# SH8_-_FORCE_SENSITIVE_RESISTOR.net
KiCad netlist of a schematic drawn in Altium Designer
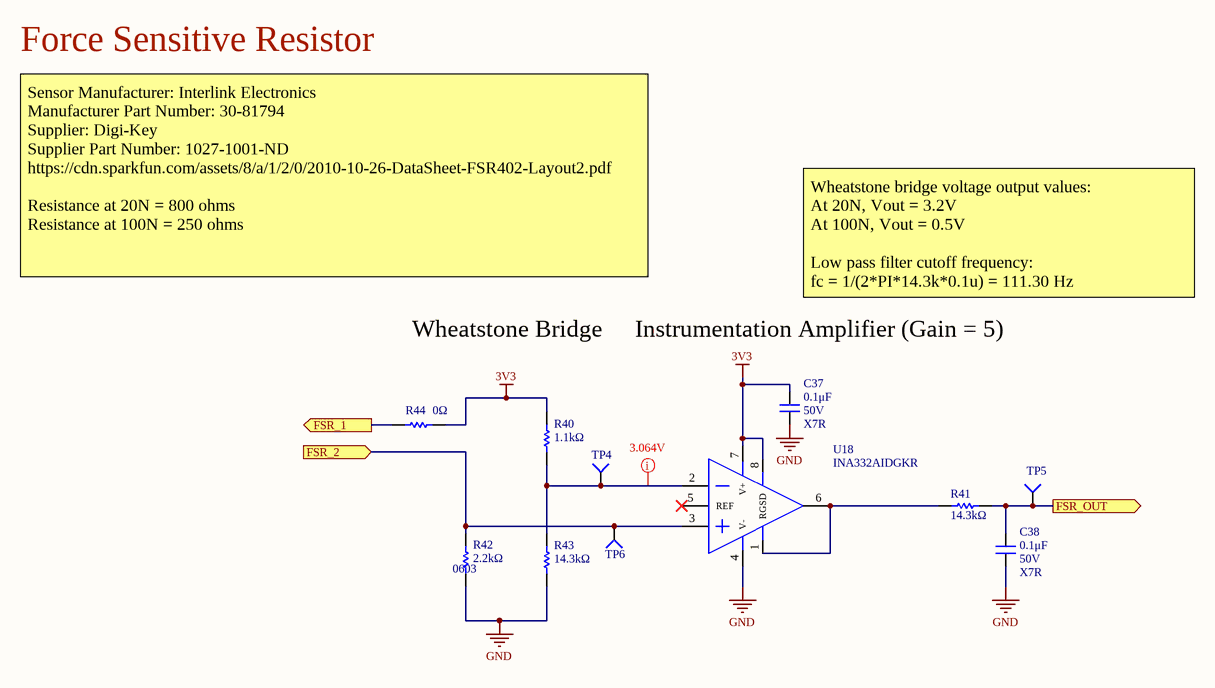
[diagram p0: SH8 - FORCE SENSITIVE RESISTOR.SchDoc]

(export (version "E")
  (design (tool "Eeschema 10.0.6"))
  (components
    (comp (ref "C37")
      (value "0.1μF")
      (footprint "CAP0603")
      (description "CAP CER 0.1UF 50V X7R 0603")
      (fields
        (field (name "VOLTAGE RATING") "50V")
        (field (name "DIELECTRIC") "X7R")
        (field (name "Comment") "CAP_0.1uF_50V_0603")
      )
      (libsource (lib "UWRT_Schematic_Library_2020") (part "CAP_0.1uF_50V_0603"))
    )
    (comp (ref "C38")
      (value "0.1μF")
      (footprint "CAP0603")
      (description "CAP CER 0.1UF 50V X7R 0603")
      (fields
        (field (name "VOLTAGE RATING") "50V")
        (field (name "DIELECTRIC") "X7R")
        (field (name "Comment") "CAP_0.1uF_50V_0603")
      )
      (libsource (lib "UWRT_Schematic_Library_2020") (part "CAP_0.1uF_50V_0603"))
    )
    (comp (ref "R40")
      (value "1.1kΩ")
      (footprint "RESC0603")
      (description "RES 1.1K OHM 1% 1/10W 0603")
      (fields (field (name "Comment") "RES_1.1kΩ_0603_1%"))
      (libsource (lib "UWRT_Schematic_Library_2020") (part "RES_1.1kΩ_0603_1%"))
    )
    (comp (ref "R41")
      (value "14.3kΩ")
      (footprint "RESC0603")
      (description "RES 14.3K OHM 1% 1/10W 0603")
      (fields (field (name "Comment") "RES_14.3kΩ_0603_1%"))
      (libsource (lib "UWRT_Schematic_Library_2020") (part "RES_14.3kΩ_0603_1%"))
    )
    (comp (ref "R42")
      (value "2.2kΩ")
      (footprint "RESC0603")
      (description "RES 2.2K OHM 1% 1/10W 0603")
      (fields (field (name "PACKAGE/FOOTPRINT") "0603") (field (name "Comment") "RES_2.2kΩ_0603_1%"))
      (libsource (lib "UWRT_Schematic_Library_2020") (part "RES_2.2kΩ_0603_1%"))
    )
    (comp (ref "R43")
      (value "14.3kΩ")
      (footprint "RESC0603")
      (description "RES 14.3K OHM 1% 1/10W 0603")
      (fields (field (name "Comment") "RES_14.3kΩ_0603_1%"))
      (libsource (lib "UWRT_Schematic_Library_2020") (part "RES_14.3kΩ_0603_1%"))
    )
    (comp (ref "R44")
      (value "0Ω")
      (footprint "RESC0603")
      (description "RES 0 OHM JUMPER 1/10W 0603")
      (fields (field (name "Comment") "RES_0Ω_0603"))
      (libsource (lib "UWRT_Schematic_Library_2020") (part "RES_0Ω_0603"))
    )
    (comp (ref "TP4")
      (value "TESTPOINT_1MM_CIRCLE")
      (footprint "TESTPOINT_CIRCLE_1MM")
      (description "TESTPOINT 1MM CIRCLE")
      (libsource (lib "UWRT_Schematic_Library_2020") (part "TESTPOINT_1MM_CIRCLE"))
    )
    (comp (ref "TP5")
      (value "TESTPOINT_1MM_CIRCLE")
      (footprint "TESTPOINT_CIRCLE_1MM")
      (description "TESTPOINT 1MM CIRCLE")
      (libsource (lib "UWRT_Schematic_Library_2020") (part "TESTPOINT_1MM_CIRCLE"))
    )
    (comp (ref "TP6")
      (value "TESTPOINT_1MM_CIRCLE")
      (footprint "TESTPOINT_CIRCLE_1MM")
      (description "TESTPOINT 1MM CIRCLE")
      (libsource (lib "UWRT_Schematic_Library_2020") (part "TESTPOINT_1MM_CIRCLE"))
    )
    (comp (ref "U18")
      (value "INA332AIDGKR")
      (footprint "INA332AIDGKR")
      (description "IC INSTRUMENTATION AMP 1 CIRCUIT 8VSSOP")
      (fields (field (name "MANUFACTURER PART NUMBER 1") "INA332AIDGKR"))
      (libsource (lib "UWRT_Schematic_Library_2020") (part "INA332AIDGKR"))
    )
  )
  (nets
    (net (code "1") (name "/FSR_1") (class "Default")
      (node (ref "R44") (pin "2") (pinfunction "2_2") (pintype "passive"))
    )
    (net (code "2") (name "/FSR_2") (class "Default")
      (node (ref "R42") (pin "2") (pinfunction "2_2") (pintype "passive"))
      (node (ref "TP6") (pin "1") (pinfunction "=value_1") (pintype "passive"))
      (node (ref "U18") (pin "3") (pinfunction "IN+_3") (pintype "passive"))
    )
    (net (code "3") (name "/FSR_OUT") (class "Default")
      (node (ref "C38") (pin "2") (pinfunction "2_2") (pintype "passive"))
      (node (ref "R41") (pin "2") (pinfunction "2_2") (pintype "passive"))
      (node (ref "TP5") (pin "1") (pinfunction "=value_1") (pintype "passive"))
    )
    (net (code "4") (name "3V3") (class "Default")
      (node (ref "C37") (pin "2") (pinfunction "2_2") (pintype "passive"))
      (node (ref "R40") (pin "2") (pinfunction "2_2") (pintype "passive"))
      (node (ref "R44") (pin "1") (pinfunction "1_1") (pintype "passive"))
      (node (ref "U18") (pin "7") (pinfunction "V+_7") (pintype "power_in"))
      (node (ref "U18") (pin "8") (pinfunction "SD_8") (pintype "power_in"))
    )
    (net (code "5") (name "GND") (class "Default")
      (node (ref "C37") (pin "1") (pinfunction "1_1") (pintype "passive"))
      (node (ref "C38") (pin "1") (pinfunction "1_1") (pintype "passive"))
      (node (ref "R42") (pin "1") (pinfunction "1_1") (pintype "passive"))
      (node (ref "R43") (pin "1") (pinfunction "1_1") (pintype "passive"))
      (node (ref "U18") (pin "4") (pinfunction "V-_4") (pintype "passive"))
    )
    (net (code "6") (name "Net-(TP4-=value)") (class "Default")
      (node (ref "R40") (pin "1") (pinfunction "1_1") (pintype "passive"))
      (node (ref "R43") (pin "2") (pinfunction "2_2") (pintype "passive"))
      (node (ref "TP4") (pin "1") (pinfunction "=value_1") (pintype "passive"))
      (node (ref "U18") (pin "2") (pinfunction "IN-_2") (pintype "passive"))
    )
    (net (code "7") (name "Net-(U18-RG)") (class "Default")
      (node (ref "R41") (pin "1") (pinfunction "1_1") (pintype "passive"))
      (node (ref "U18") (pin "1") (pinfunction "RG_1") (pintype "power_in"))
      (node (ref "U18") (pin "6") (pinfunction "Vout_6") (pintype "passive"))
    )
    (net (code "8") (name "unconnected-(U18-REF-Pad5)") (class "Default")
      (node (ref "U18") (pin "5") (pinfunction "REF_5") (pintype "power_in+no_connect"))
    )
  )
)
